# chaoswest-token.net
KiCad netlist of a schematic drawn in EAGLE
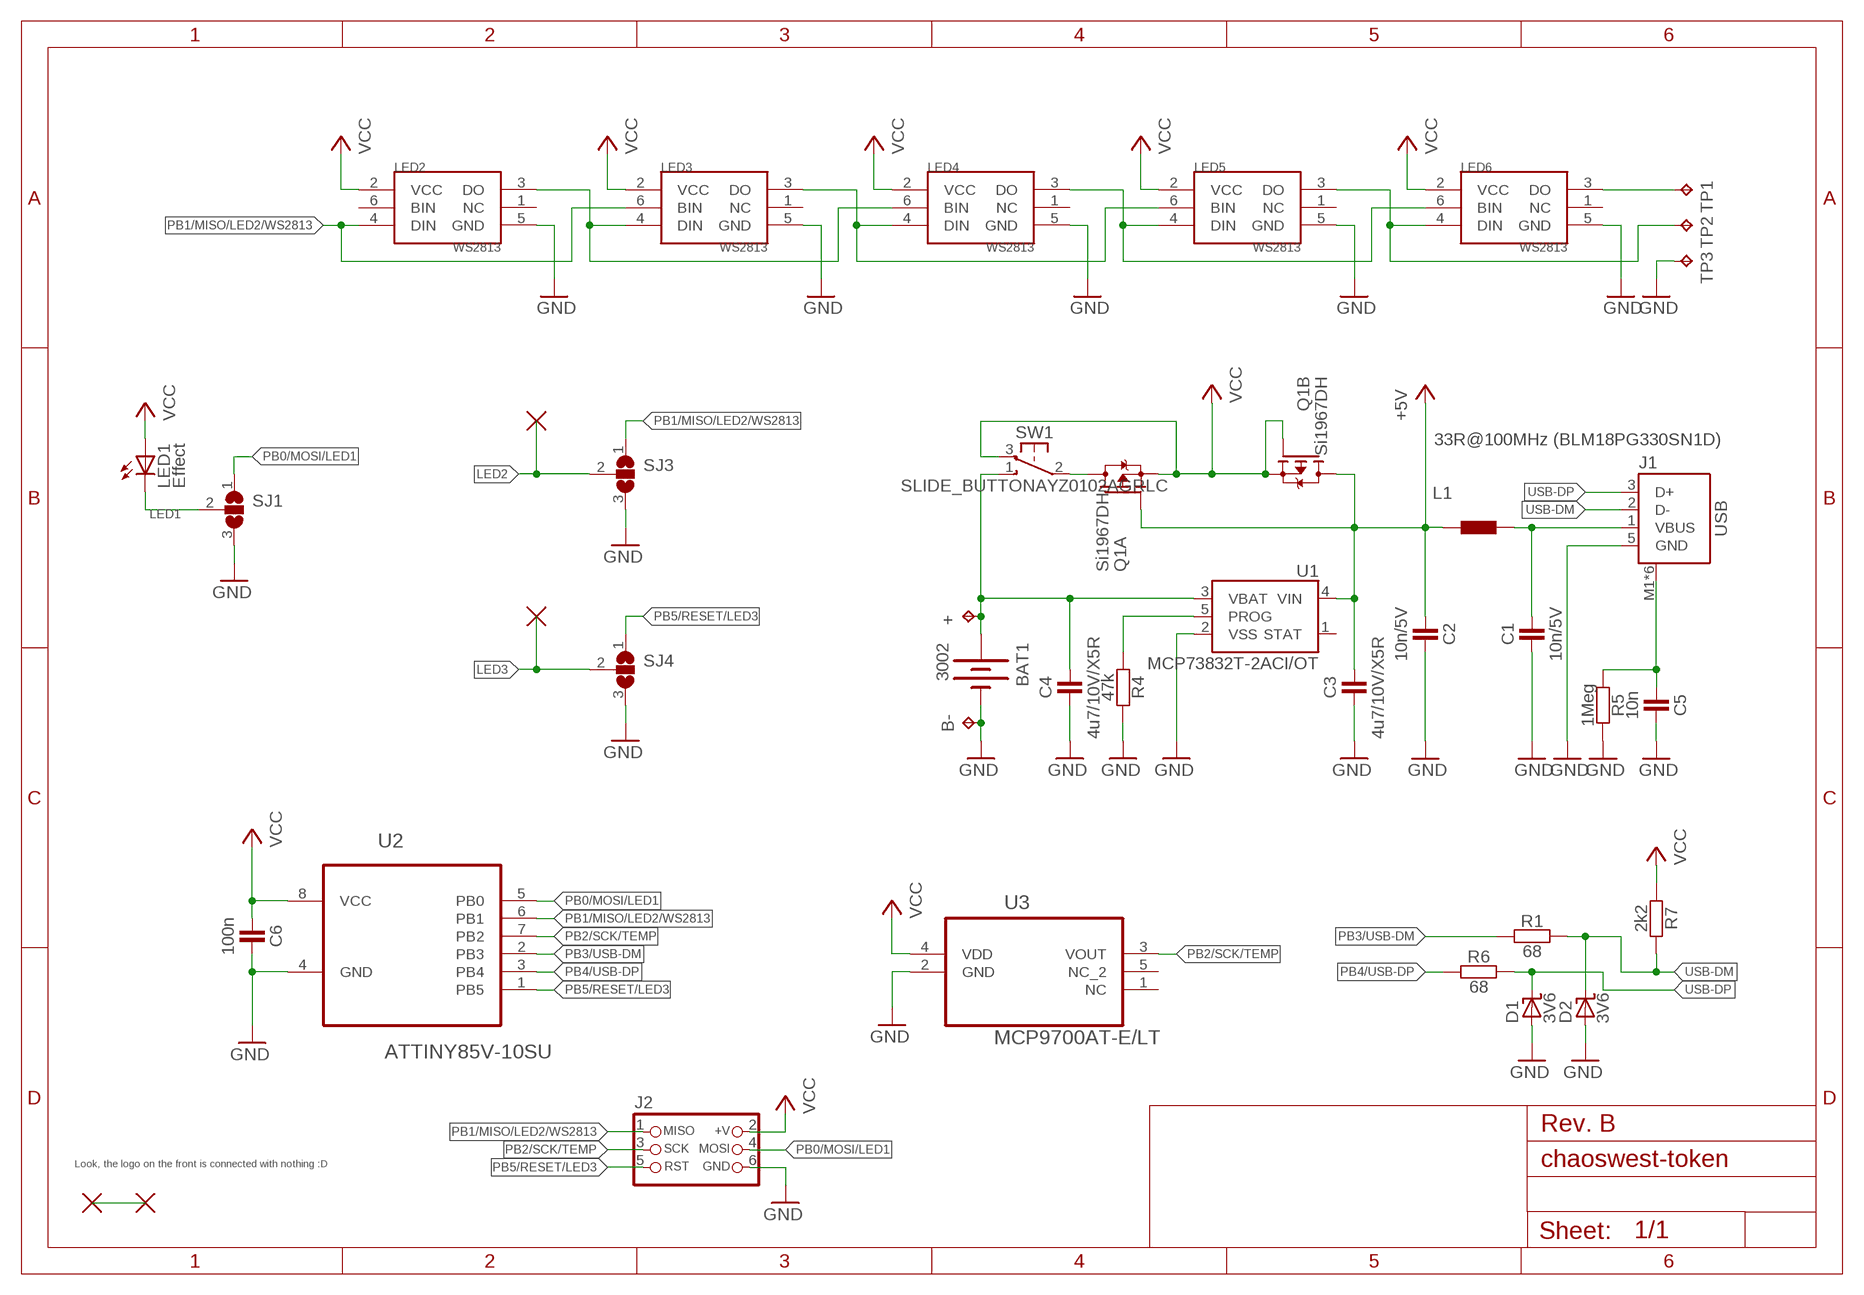
[diagram p0: schematic, sheet 1]

(export (version "E")
  (design (tool "Eeschema 10.0.6"))
  (components
    (comp (ref "+")
      (value "TPTP18SQ")
      (footprint "eagle-import:TP18SQ")
      (libsource (lib "eagle-import") (part "TPTP18SQ"))
    )
    (comp (ref "B-")
      (value "TPTP18SQ")
      (footprint "eagle-import:TP18SQ")
      (libsource (lib "eagle-import") (part "TPTP18SQ"))
    )
    (comp (ref "BAT1")
      (value "3002")
      (footprint "eagle-import:BATTCON_20MM")
      (libsource (lib "eagle-import") (part "3002"))
    )
    (comp (ref "C1")
      (value "10n/5V")
      (footprint "eagle-import:C0805")
      (libsource (lib "eagle-import") (part "CAPACITOR-0805"))
    )
    (comp (ref "C2")
      (value "10n/5V")
      (footprint "eagle-import:C0805")
      (libsource (lib "eagle-import") (part "CAPACITOR-0805"))
    )
    (comp (ref "C3")
      (value "4u7/10V/X5R")
      (footprint "eagle-import:C0805")
      (libsource (lib "eagle-import") (part "CAPACITOR-0805"))
    )
    (comp (ref "C4")
      (value "4u7/10V/X5R")
      (footprint "eagle-import:C0805")
      (libsource (lib "eagle-import") (part "CAPACITOR-0805"))
    )
    (comp (ref "C5")
      (value "10n")
      (footprint "eagle-import:C0805")
      (libsource (lib "eagle-import") (part "CAPACITOR-0805"))
    )
    (comp (ref "C6")
      (value "100n")
      (footprint "eagle-import:C0805")
      (libsource (lib "eagle-import") (part "CAPACITOR-0805"))
    )
    (comp (ref "D1")
      (value "3V6")
      (footprint "eagle-import:SOD123")
      (libsource (lib "eagle-import") (part "D_ZENER-SOD123"))
    )
    (comp (ref "D2")
      (value "3V6")
      (footprint "eagle-import:SOD123")
      (libsource (lib "eagle-import") (part "D_ZENER-SOD123"))
    )
    (comp (ref "J1")
      (value "USB")
      (footprint "eagle-import:MOLEX_47346-0001")
      (fields (field (name "MPN") "47346-0001"))
      (libsource (lib "eagle-import") (part "47346-0001"))
    )
    (comp (ref "J2")
      (value "ISP")
      (footprint "eagle-import:M2X3_SMD")
      (libsource (lib "eagle-import") (part "CON_HEADER_PRG_AVR_ICSP-SMD"))
    )
    (comp (ref "L1")
      (value "33R@100MHz (BLM18PG330SN1D)")
      (footprint "eagle-import:C0805")
      (libsource (lib "eagle-import") (part "INDUCTOR-0805"))
    )
    (comp (ref "LED1")
      (value "Effect")
      (footprint "eagle-import:LED5MM")
      (libsource (lib "eagle-import") (part "LED5MM"))
    )
    (comp (ref "LED2")
      (value "WS2813")
      (footprint "eagle-import:WS2813")
      (libsource (lib "eagle-import") (part "WS2813"))
    )
    (comp (ref "LED3")
      (value "WS2813")
      (footprint "eagle-import:WS2813")
      (libsource (lib "eagle-import") (part "WS2813"))
    )
    (comp (ref "LED4")
      (value "WS2813")
      (footprint "eagle-import:WS2813")
      (libsource (lib "eagle-import") (part "WS2813"))
    )
    (comp (ref "LED5")
      (value "WS2813")
      (footprint "eagle-import:WS2813")
      (libsource (lib "eagle-import") (part "WS2813"))
    )
    (comp (ref "LED6")
      (value "WS2813")
      (footprint "eagle-import:WS2813")
      (libsource (lib "eagle-import") (part "WS2813"))
    )
    (comp (ref "Q1")
      (value "Si1967DH")
      (footprint "eagle-import:SOT363")
      (libsource (lib "eagle-import") (part "BSS84AKS"))
    )
    (comp (ref "R1")
      (value "68")
      (footprint "eagle-import:C0805")
      (libsource (lib "eagle-import") (part "RESISTOR-0805"))
    )
    (comp (ref "R4")
      (value "47k")
      (footprint "eagle-import:C0805")
      (libsource (lib "eagle-import") (part "RESISTOR-0805"))
    )
    (comp (ref "R5")
      (value "1Meg")
      (footprint "eagle-import:C0805")
      (libsource (lib "eagle-import") (part "RESISTOR-0805"))
    )
    (comp (ref "R6")
      (value "68")
      (footprint "eagle-import:C0805")
      (libsource (lib "eagle-import") (part "RESISTOR-0805"))
    )
    (comp (ref "R7")
      (value "2k2")
      (footprint "eagle-import:C0805")
      (libsource (lib "eagle-import") (part "RESISTOR-0805"))
    )
    (comp (ref "SJ1")
      (value "SJ2W")
      (footprint "eagle-import:SJ_2")
      (libsource (lib "eagle-import") (part "SJ2W"))
    )
    (comp (ref "SJ3")
      (value "SJ2W")
      (footprint "eagle-import:SJ_2")
      (libsource (lib "eagle-import") (part "SJ2W"))
    )
    (comp (ref "SJ4")
      (value "SJ2W")
      (footprint "eagle-import:SJ_2")
      (libsource (lib "eagle-import") (part "SJ2W"))
    )
    (comp (ref "SW1")
      (value "SLIDE_BUTTONAYZ0102AGRLC")
      (footprint "eagle-import:AYZ0102AGRLC")
      (libsource (lib "eagle-import") (part "SLIDE_BUTTONAYZ0102AGRLC"))
    )
    (comp (ref "TP1")
      (value "DO")
      (footprint "eagle-import:TP09SQ")
      (libsource (lib "eagle-import") (part "TPTP09SQ"))
    )
    (comp (ref "TP2")
      (value "BO")
      (footprint "eagle-import:TP09SQ")
      (libsource (lib "eagle-import") (part "TPTP09SQ"))
    )
    (comp (ref "TP3")
      (value "GND")
      (footprint "eagle-import:TP09SQ")
      (libsource (lib "eagle-import") (part "TPTP09SQ"))
    )
    (comp (ref "U$1")
      (value "EMPTY_SIGNAL")
      (footprint "eagle-import:SMALLSPOT")
      (libsource (lib "eagle-import") (part "EMPTY_SIGNAL"))
    )
    (comp (ref "U$2")
      (value "EMPTY_SIGNAL")
      (footprint "eagle-import:SMALLSPOT")
      (libsource (lib "eagle-import") (part "EMPTY_SIGNAL"))
    )
    (comp (ref "U$3")
      (value "EMPTY_SIGNAL")
      (footprint "eagle-import:SMALLSPOT")
      (libsource (lib "eagle-import") (part "EMPTY_SIGNAL"))
    )
    (comp (ref "U$4")
      (value "EMPTY_SIGNAL")
      (footprint "eagle-import:SMALLSPOT")
      (libsource (lib "eagle-import") (part "EMPTY_SIGNAL"))
    )
    (comp (ref "U1")
      (value "MCP73832T-2ACI/OT")
      (footprint "eagle-import:SOT23-5")
      (libsource (lib "eagle-import") (part "MCP73831"))
    )
    (comp (ref "U2")
      (value "ATTINY85V-10SU")
      (footprint "eagle-import:SOIC127P798X216-8N")
      (libsource (lib "eagle-import") (part "ATTINY85V-10SU"))
    )
    (comp (ref "U3")
      (value "MCP9700AT-E/LT")
      (footprint "eagle-import:SOT65P210X110-5N")
      (libsource (lib "eagle-import") (part "MCP9700AT-E/LT"))
    )
  )
  (nets
    (net (code "1") (name "+5V") (class "Default")
      (node (ref "C2") (pin "1") (pinfunction "1_1") (pintype "passive"))
      (node (ref "C3") (pin "1") (pinfunction "1_1") (pintype "passive"))
      (node (ref "L1") (pin "2") (pinfunction "2_2") (pintype "passive"))
      (node (ref "Q1") (pin "2") (pinfunction "G_2") (pintype "passive"))
      (node (ref "Q1") (pin "3") (pinfunction "D_3") (pintype "passive"))
      (node (ref "U1") (pin "4") (pinfunction "VIN_4") (pintype "power_in"))
    )
    (net (code "2") (name "/LED1") (class "Default")
      (node (ref "LED1") (pin "K") (pinfunction "C_K") (pintype "passive"))
      (node (ref "SJ1") (pin "2") (pinfunction "2_2") (pintype "passive"))
    )
    (net (code "3") (name "GND") (class "Default")
      (node (ref "B-") (pin "TP") (pinfunction "TP_TP") (pintype "input"))
      (node (ref "BAT1") (pin "-") (pinfunction "-_-") (pintype "power_in"))
      (node (ref "C1") (pin "2") (pinfunction "2_2") (pintype "passive"))
      (node (ref "C2") (pin "2") (pinfunction "2_2") (pintype "passive"))
      (node (ref "C3") (pin "2") (pinfunction "2_2") (pintype "passive"))
      (node (ref "C4") (pin "2") (pinfunction "2_2") (pintype "passive"))
      (node (ref "C5") (pin "2") (pinfunction "2_2") (pintype "passive"))
      (node (ref "C6") (pin "2") (pinfunction "2_2") (pintype "passive"))
      (node (ref "D1") (pin "A") (pinfunction "A_A") (pintype "passive"))
      (node (ref "D2") (pin "A") (pinfunction "A_A") (pintype "passive"))
      (node (ref "J1") (pin "5") (pinfunction "GND_5") (pintype "power_in"))
      (node (ref "J2") (pin "6") (pinfunction "GND_6") (pintype "passive"))
      (node (ref "LED2") (pin "5") (pinfunction "GND_5") (pintype "power_in"))
      (node (ref "LED3") (pin "5") (pinfunction "GND_5") (pintype "power_in"))
      (node (ref "LED4") (pin "5") (pinfunction "GND_5") (pintype "power_in"))
      (node (ref "LED5") (pin "5") (pinfunction "GND_5") (pintype "power_in"))
      (node (ref "LED6") (pin "5") (pinfunction "GND_5") (pintype "power_in"))
      (node (ref "R4") (pin "1") (pinfunction "1_1") (pintype "passive"))
      (node (ref "R5") (pin "1") (pinfunction "1_1") (pintype "passive"))
      (node (ref "SJ1") (pin "3") (pinfunction "3_3") (pintype "passive"))
      (node (ref "SJ3") (pin "3") (pinfunction "3_3") (pintype "passive"))
      (node (ref "SJ4") (pin "3") (pinfunction "3_3") (pintype "passive"))
      (node (ref "TP3") (pin "TP") (pinfunction "TP_TP") (pintype "input"))
      (node (ref "U1") (pin "2") (pinfunction "VSS_2") (pintype "power_in"))
      (node (ref "U2") (pin "4") (pinfunction "GND_4") (pintype "passive"))
      (node (ref "U3") (pin "2") (pinfunction "GND_2") (pintype "passive"))
    )
    (net (code "4") (name "LED2") (class "Default")
      (node (ref "SJ3") (pin "2") (pinfunction "2_2") (pintype "passive"))
      (node (ref "U$3") (pin "X") (pinfunction "X_X") (pintype "bidirectional"))
    )
    (net (code "5") (name "LED3") (class "Default")
      (node (ref "SJ4") (pin "2") (pinfunction "2_2") (pintype "passive"))
      (node (ref "U$4") (pin "X") (pinfunction "X_X") (pintype "bidirectional"))
    )
    (net (code "6") (name "Net-(C5-Pad1)") (class "Default")
      (node (ref "C5") (pin "1") (pinfunction "1_1") (pintype "passive"))
      (node (ref "J1") (pin "M1") (pinfunction "SHIELD_M1") (pintype "passive"))
      (node (ref "J1") (pin "M2") (pinfunction "SHIELD_M2") (pintype "passive"))
      (node (ref "J1") (pin "M3") (pinfunction "SHIELD_M3") (pintype "passive"))
      (node (ref "J1") (pin "M4") (pinfunction "SHIELD_M4") (pintype "passive"))
      (node (ref "J1") (pin "M5") (pinfunction "SHIELD_M5") (pintype "passive"))
      (node (ref "J1") (pin "M6") (pinfunction "SHIELD_M6") (pintype "passive"))
      (node (ref "R5") (pin "2") (pinfunction "2_2") (pintype "passive"))
    )
    (net (code "7") (name "Net-(J1-VBUS)") (class "Default")
      (node (ref "C1") (pin "1") (pinfunction "1_1") (pintype "passive"))
      (node (ref "J1") (pin "1") (pinfunction "VBUS_1") (pintype "power_in"))
      (node (ref "L1") (pin "1") (pinfunction "1_1") (pintype "passive"))
    )
    (net (code "8") (name "Net-(LED2-DO)") (class "Default")
      (node (ref "LED2") (pin "3") (pinfunction "DO_3") (pintype "bidirectional"))
      (node (ref "LED3") (pin "4") (pinfunction "DIN_4") (pintype "bidirectional"))
      (node (ref "LED4") (pin "6") (pinfunction "BIN_6") (pintype "bidirectional"))
    )
    (net (code "9") (name "Net-(LED3-DO)") (class "Default")
      (node (ref "LED3") (pin "3") (pinfunction "DO_3") (pintype "bidirectional"))
      (node (ref "LED4") (pin "4") (pinfunction "DIN_4") (pintype "bidirectional"))
      (node (ref "LED5") (pin "6") (pinfunction "BIN_6") (pintype "bidirectional"))
    )
    (net (code "10") (name "Net-(LED4-DO)") (class "Default")
      (node (ref "LED4") (pin "3") (pinfunction "DO_3") (pintype "bidirectional"))
      (node (ref "LED5") (pin "4") (pinfunction "DIN_4") (pintype "bidirectional"))
      (node (ref "LED6") (pin "6") (pinfunction "BIN_6") (pintype "bidirectional"))
    )
    (net (code "11") (name "Net-(LED5-DO)") (class "Default")
      (node (ref "LED5") (pin "3") (pinfunction "DO_3") (pintype "bidirectional"))
      (node (ref "LED6") (pin "4") (pinfunction "DIN_4") (pintype "bidirectional"))
      (node (ref "TP2") (pin "TP") (pinfunction "TP_TP") (pintype "input"))
    )
    (net (code "12") (name "Net-(LED6-DO)") (class "Default")
      (node (ref "LED6") (pin "3") (pinfunction "DO_3") (pintype "bidirectional"))
      (node (ref "TP1") (pin "TP") (pinfunction "TP_TP") (pintype "input"))
    )
    (net (code "13") (name "Net-(Q1A-D)") (class "Default")
      (node (ref "Q1") (pin "6") (pinfunction "D_6") (pintype "passive"))
      (node (ref "SW1") (pin "2") (pinfunction "P1_2") (pintype "passive"))
    )
    (net (code "14") (name "Net-(SW1-S1)") (class "Default")
      (node (ref "+") (pin "TP") (pinfunction "TP_TP") (pintype "input"))
      (node (ref "BAT1") (pin "+1") (pinfunction "+_+1") (pintype "power_in"))
      (node (ref "BAT1") (pin "+2") (pinfunction "+_+2") (pintype "power_in"))
      (node (ref "C4") (pin "1") (pinfunction "1_1") (pintype "passive"))
      (node (ref "SW1") (pin "1") (pinfunction "S1_1") (pintype "passive"))
      (node (ref "U1") (pin "3") (pinfunction "VBAT_3") (pintype "power_in"))
    )
    (net (code "15") (name "Net-(U$1-PadX)") (class "Default")
      (node (ref "U$1") (pin "X") (pinfunction "X_X") (pintype "bidirectional"))
      (node (ref "U$2") (pin "X") (pinfunction "X_X") (pintype "bidirectional"))
    )
    (net (code "16") (name "Net-(U1-PROG)") (class "Default")
      (node (ref "R4") (pin "2") (pinfunction "2_2") (pintype "passive"))
      (node (ref "U1") (pin "5") (pinfunction "PROG_5") (pintype "input"))
    )
    (net (code "17") (name "PB0{slash}MOSI{slash}LED1") (class "Default")
      (node (ref "J2") (pin "4") (pinfunction "MOSI_4") (pintype "passive"))
      (node (ref "SJ1") (pin "1") (pinfunction "1_1") (pintype "passive"))
      (node (ref "U2") (pin "5") (pinfunction "PB0_5") (pintype "bidirectional"))
    )
    (net (code "18") (name "PB1{slash}MISO{slash}LED2{slash}WS2813") (class "Default")
      (node (ref "J2") (pin "1") (pinfunction "MISO_1") (pintype "passive"))
      (node (ref "LED2") (pin "4") (pinfunction "DIN_4") (pintype "bidirectional"))
      (node (ref "LED3") (pin "6") (pinfunction "BIN_6") (pintype "bidirectional"))
      (node (ref "SJ3") (pin "1") (pinfunction "1_1") (pintype "passive"))
      (node (ref "U2") (pin "6") (pinfunction "PB1_6") (pintype "bidirectional"))
    )
    (net (code "19") (name "PB2{slash}SCK{slash}TEMP") (class "Default")
      (node (ref "J2") (pin "3") (pinfunction "SCK_3") (pintype "passive"))
      (node (ref "U2") (pin "7") (pinfunction "PB2_7") (pintype "bidirectional"))
      (node (ref "U3") (pin "3") (pinfunction "VOUT_3") (pintype "output"))
    )
    (net (code "20") (name "PB3{slash}USB-DM") (class "Default")
      (node (ref "R1") (pin "2") (pinfunction "2_2") (pintype "passive"))
      (node (ref "U2") (pin "2") (pinfunction "PB3_2") (pintype "bidirectional"))
    )
    (net (code "21") (name "PB4{slash}USB-DP") (class "Default")
      (node (ref "R6") (pin "2") (pinfunction "2_2") (pintype "passive"))
      (node (ref "U2") (pin "3") (pinfunction "PB4_3") (pintype "bidirectional"))
    )
    (net (code "22") (name "PB5{slash}RESET{slash}LED3") (class "Default")
      (node (ref "J2") (pin "5") (pinfunction "RST_5") (pintype "passive"))
      (node (ref "SJ4") (pin "1") (pinfunction "1_1") (pintype "passive"))
      (node (ref "U2") (pin "1") (pinfunction "PB5_1") (pintype "bidirectional"))
    )
    (net (code "23") (name "USB-DM") (class "Default")
      (node (ref "D2") (pin "C") (pinfunction "C_C") (pintype "passive"))
      (node (ref "J1") (pin "2") (pinfunction "D-_2") (pintype "bidirectional"))
      (node (ref "R1") (pin "1") (pinfunction "1_1") (pintype "passive"))
      (node (ref "R7") (pin "1") (pinfunction "1_1") (pintype "passive"))
    )
    (net (code "24") (name "USB-DP") (class "Default")
      (node (ref "D1") (pin "C") (pinfunction "C_C") (pintype "passive"))
      (node (ref "J1") (pin "3") (pinfunction "D+_3") (pintype "bidirectional"))
      (node (ref "R6") (pin "1") (pinfunction "1_1") (pintype "passive"))
    )
    (net (code "25") (name "VCC") (class "Default")
      (node (ref "C6") (pin "1") (pinfunction "1_1") (pintype "passive"))
      (node (ref "J2") (pin "2") (pinfunction "+V_2") (pintype "passive"))
      (node (ref "LED1") (pin "A") (pinfunction "A_A") (pintype "passive"))
      (node (ref "LED2") (pin "2") (pinfunction "VCC_2") (pintype "power_in"))
      (node (ref "LED3") (pin "2") (pinfunction "VCC_2") (pintype "power_in"))
      (node (ref "LED4") (pin "2") (pinfunction "VCC_2") (pintype "power_in"))
      (node (ref "LED5") (pin "2") (pinfunction "VCC_2") (pintype "power_in"))
      (node (ref "LED6") (pin "2") (pinfunction "VCC_2") (pintype "power_in"))
      (node (ref "Q1") (pin "1") (pinfunction "S_1") (pintype "passive"))
      (node (ref "Q1") (pin "4") (pinfunction "S_4") (pintype "passive"))
      (node (ref "Q1") (pin "5") (pinfunction "G_5") (pintype "passive"))
      (node (ref "R7") (pin "2") (pinfunction "2_2") (pintype "passive"))
      (node (ref "SW1") (pin "3") (pinfunction "O1_3") (pintype "passive"))
      (node (ref "U2") (pin "8") (pinfunction "VCC_8") (pintype "power_in"))
      (node (ref "U3") (pin "4") (pinfunction "VDD_4") (pintype "power_in"))
    )
    (net (code "26") (name "unconnected-(LED2-BIN-Pad6)") (class "Default")
      (node (ref "LED2") (pin "6") (pinfunction "BIN_6") (pintype "bidirectional"))
    )
    (net (code "27") (name "unconnected-(LED2-NC-Pad1)") (class "Default")
      (node (ref "LED2") (pin "1") (pinfunction "NC_1") (pintype "no_connect"))
    )
    (net (code "28") (name "unconnected-(LED3-NC-Pad1)") (class "Default")
      (node (ref "LED3") (pin "1") (pinfunction "NC_1") (pintype "no_connect"))
    )
    (net (code "29") (name "unconnected-(LED4-NC-Pad1)") (class "Default")
      (node (ref "LED4") (pin "1") (pinfunction "NC_1") (pintype "no_connect"))
    )
    (net (code "30") (name "unconnected-(LED5-NC-Pad1)") (class "Default")
      (node (ref "LED5") (pin "1") (pinfunction "NC_1") (pintype "no_connect"))
    )
    (net (code "31") (name "unconnected-(LED6-NC-Pad1)") (class "Default")
      (node (ref "LED6") (pin "1") (pinfunction "NC_1") (pintype "no_connect"))
    )
    (net (code "32") (name "unconnected-(U1-STAT-Pad1)") (class "Default")
      (node (ref "U1") (pin "1") (pinfunction "STAT_1") (pintype "output"))
    )
    (net (code "33") (name "unconnected-(U3-NC-Pad1)") (class "Default")
      (node (ref "U3") (pin "1") (pinfunction "NC_1") (pintype "no_connect"))
    )
    (net (code "34") (name "unconnected-(U3-NC_2-Pad5)") (class "Default")
      (node (ref "U3") (pin "5") (pinfunction "NC_2_5") (pintype "no_connect"))
    )
  )
)
